# ir_remote_v3.net
KiCad netlist of a schematic drawn in EAGLE
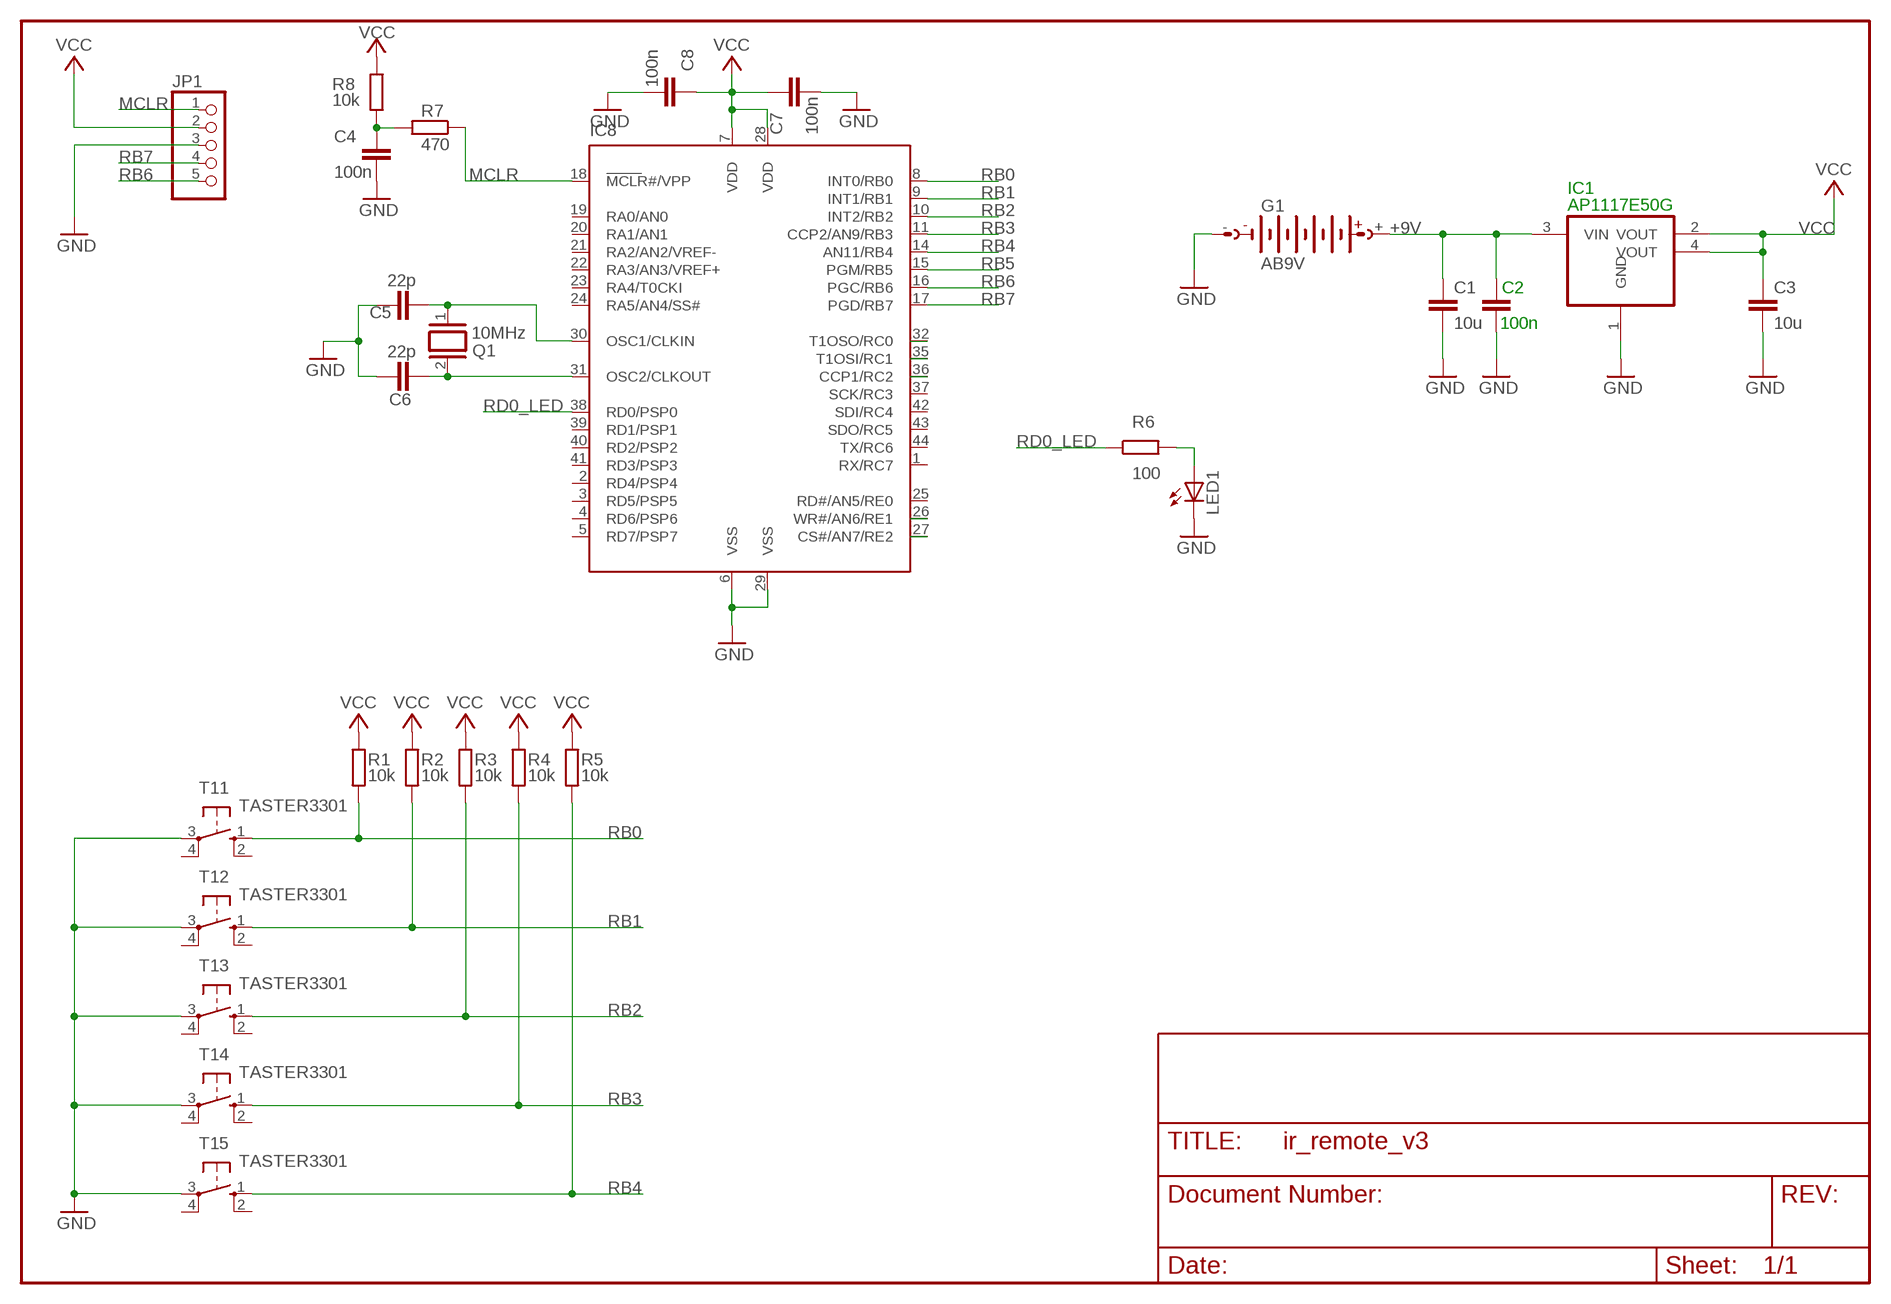
[diagram p0: schematic, sheet 1]

(export (version "E")
  (design (tool "Eeschema 10.0.6"))
  (components
    (comp (ref "C1")
      (value "10u")
      (footprint "eagle-import:C0805")
      (libsource (lib "eagle-import") (part "C-EUC0805"))
    )
    (comp (ref "C2")
      (value "100n")
      (footprint "eagle-import:C0805")
      (libsource (lib "eagle-import") (part "rcl_416_C-EUC0805"))
    )
    (comp (ref "C3")
      (value "10u")
      (footprint "eagle-import:C0805")
      (libsource (lib "eagle-import") (part "C-EUC0805"))
    )
    (comp (ref "C4")
      (value "100n")
      (footprint "eagle-import:C0805")
      (libsource (lib "eagle-import") (part "C-EUC0805"))
    )
    (comp (ref "C5")
      (value "22p")
      (footprint "eagle-import:C0603_WE")
      (libsource (lib "eagle-import") (part "C-EUC0603_WE"))
    )
    (comp (ref "C6")
      (value "22p")
      (footprint "eagle-import:C0603_WE")
      (libsource (lib "eagle-import") (part "C-EUC0603_WE"))
    )
    (comp (ref "C7")
      (value "100n")
      (footprint "eagle-import:C0805")
      (libsource (lib "eagle-import") (part "C-EUC0805"))
    )
    (comp (ref "C8")
      (value "100n")
      (footprint "eagle-import:C0805")
      (libsource (lib "eagle-import") (part "C-EUC0805"))
    )
    (comp (ref "G1")
      (value "AB9V")
      (footprint "eagle-import:AB9V")
      (libsource (lib "eagle-import") (part "AB9V"))
    )
    (comp (ref "IC1")
      (value "AP1117E50G")
      (footprint "eagle-import:SOT223")
      (libsource (lib "eagle-import") (part "REG1117-2OUT"))
    )
    (comp (ref "IC8")
      (value "PIC18F4520")
      (footprint "eagle-import:TQFP44")
      (libsource (lib "eagle-import") (part "PIC18F4520"))
    )
    (comp (ref "JP1")
      (value "PINHD-1X5")
      (footprint "eagle-import:1X05")
      (libsource (lib "eagle-import") (part "PINHD-1X5"))
    )
    (comp (ref "LED1")
      (value "LED5MM")
      (footprint "eagle-import:LED5MM")
      (libsource (lib "eagle-import") (part "LED5MM"))
    )
    (comp (ref "Q1")
      (value "10MHz")
      (footprint "eagle-import:QUARZ_HC5032_2")
      (libsource (lib "eagle-import") (part "XTAL_HC5032"))
    )
    (comp (ref "R1")
      (value "10k")
      (footprint "eagle-import:M0805")
      (libsource (lib "eagle-import") (part "R-EU_M0805"))
    )
    (comp (ref "R2")
      (value "10k")
      (footprint "eagle-import:M0805")
      (libsource (lib "eagle-import") (part "R-EU_M0805"))
    )
    (comp (ref "R3")
      (value "10k")
      (footprint "eagle-import:M0805")
      (libsource (lib "eagle-import") (part "R-EU_M0805"))
    )
    (comp (ref "R4")
      (value "10k")
      (footprint "eagle-import:M0805")
      (libsource (lib "eagle-import") (part "R-EU_M0805"))
    )
    (comp (ref "R5")
      (value "10k")
      (footprint "eagle-import:M0805")
      (libsource (lib "eagle-import") (part "R-EU_M0805"))
    )
    (comp (ref "R6")
      (value "100")
      (footprint "eagle-import:M0805")
      (libsource (lib "eagle-import") (part "R-EU_M0805"))
    )
    (comp (ref "R7")
      (value "470")
      (footprint "eagle-import:M0805")
      (libsource (lib "eagle-import") (part "R-EU_M0805"))
    )
    (comp (ref "R8")
      (value "10k")
      (footprint "eagle-import:M0805")
      (libsource (lib "eagle-import") (part "R-EU_M0805"))
    )
    (comp (ref "T11")
      (value "TASTER3301")
      (footprint "eagle-import:TASTER3301")
      (libsource (lib "eagle-import") (part "TASTER3301"))
    )
    (comp (ref "T12")
      (value "TASTER3301")
      (footprint "eagle-import:TASTER3301")
      (libsource (lib "eagle-import") (part "TASTER3301"))
    )
    (comp (ref "T13")
      (value "TASTER3301")
      (footprint "eagle-import:TASTER3301")
      (libsource (lib "eagle-import") (part "TASTER3301"))
    )
    (comp (ref "T14")
      (value "TASTER3301")
      (footprint "eagle-import:TASTER3301")
      (libsource (lib "eagle-import") (part "TASTER3301"))
    )
    (comp (ref "T15")
      (value "TASTER3301")
      (footprint "eagle-import:TASTER3301")
      (libsource (lib "eagle-import") (part "TASTER3301"))
    )
  )
  (nets
    (net (code "1") (name "/+9V") (class "Default")
      (node (ref "C1") (pin "1") (pinfunction "1_1") (pintype "passive"))
      (node (ref "C2") (pin "1") (pinfunction "1_1") (pintype "passive"))
      (node (ref "G1") (pin "+") (pinfunction "+_+") (pintype "passive"))
      (node (ref "IC1") (pin "3") (pinfunction "VIN_3") (pintype "input"))
    )
    (net (code "2") (name "/MCLR") (class "Default")
      (node (ref "IC8") (pin "18") (pinfunction "MCLR#/VPP_18") (pintype "input"))
      (node (ref "JP1") (pin "1") (pinfunction "1_1") (pintype "passive"))
      (node (ref "R7") (pin "1") (pinfunction "1_1") (pintype "passive"))
    )
    (net (code "3") (name "/RB0") (class "Default")
      (node (ref "IC8") (pin "8") (pinfunction "INT0/RB0_8") (pintype "bidirectional"))
      (node (ref "R1") (pin "2") (pinfunction "2_2") (pintype "passive"))
      (node (ref "T11") (pin "1") (pinfunction "S_1") (pintype "passive"))
    )
    (net (code "4") (name "/RB1") (class "Default")
      (node (ref "IC8") (pin "35") (pinfunction "T1OSI/RC1_35") (pintype "bidirectional"))
      (node (ref "IC8") (pin "9") (pinfunction "INT1/RB1_9") (pintype "bidirectional"))
      (node (ref "R2") (pin "2") (pinfunction "2_2") (pintype "passive"))
      (node (ref "T12") (pin "1") (pinfunction "S_1") (pintype "passive"))
    )
    (net (code "5") (name "/RB2") (class "Default")
      (node (ref "IC8") (pin "10") (pinfunction "INT2/RB2_10") (pintype "bidirectional"))
      (node (ref "IC8") (pin "32") (pinfunction "T1OSO/RC0_32") (pintype "bidirectional"))
      (node (ref "R3") (pin "2") (pinfunction "2_2") (pintype "passive"))
      (node (ref "T13") (pin "1") (pinfunction "S_1") (pintype "passive"))
    )
    (net (code "6") (name "/RB3") (class "Default")
      (node (ref "IC8") (pin "11") (pinfunction "CCP2/AN9/RB3_11") (pintype "bidirectional"))
      (node (ref "R4") (pin "2") (pinfunction "2_2") (pintype "passive"))
      (node (ref "T14") (pin "1") (pinfunction "S_1") (pintype "passive"))
    )
    (net (code "7") (name "/RB4") (class "Default")
      (node (ref "IC8") (pin "14") (pinfunction "AN11/RB4_14") (pintype "bidirectional"))
      (node (ref "R5") (pin "2") (pinfunction "2_2") (pintype "passive"))
      (node (ref "T15") (pin "1") (pinfunction "S_1") (pintype "passive"))
    )
    (net (code "8") (name "/RB5") (class "Default")
      (node (ref "IC8") (pin "15") (pinfunction "PGM/RB5_15") (pintype "bidirectional"))
    )
    (net (code "9") (name "/RB6") (class "Default")
      (node (ref "IC8") (pin "16") (pinfunction "PGC/RB6_16") (pintype "bidirectional"))
      (node (ref "JP1") (pin "5") (pinfunction "5_5") (pintype "passive"))
    )
    (net (code "10") (name "/RB7") (class "Default")
      (node (ref "IC8") (pin "17") (pinfunction "PGD/RB7_17") (pintype "bidirectional"))
      (node (ref "JP1") (pin "4") (pinfunction "4_4") (pintype "passive"))
    )
    (net (code "11") (name "/RD0_LED") (class "Default")
      (node (ref "IC8") (pin "38") (pinfunction "RD0/PSP0_38") (pintype "bidirectional"))
      (node (ref "R6") (pin "1") (pinfunction "1_1") (pintype "passive"))
    )
    (net (code "12") (name "GND") (class "Default")
      (node (ref "C1") (pin "2") (pinfunction "2_2") (pintype "passive"))
      (node (ref "C2") (pin "2") (pinfunction "2_2") (pintype "passive"))
      (node (ref "C3") (pin "2") (pinfunction "2_2") (pintype "passive"))
      (node (ref "C4") (pin "2") (pinfunction "2_2") (pintype "passive"))
      (node (ref "C5") (pin "1") (pinfunction "1_1") (pintype "passive"))
      (node (ref "C6") (pin "1") (pinfunction "1_1") (pintype "passive"))
      (node (ref "C7") (pin "2") (pinfunction "2_2") (pintype "passive"))
      (node (ref "C8") (pin "2") (pinfunction "2_2") (pintype "passive"))
      (node (ref "G1") (pin "-") (pinfunction "-_-") (pintype "passive"))
      (node (ref "IC1") (pin "1") (pinfunction "GND_1") (pintype "power_in"))
      (node (ref "IC8") (pin "29") (pinfunction "VSS_29") (pintype "bidirectional"))
      (node (ref "IC8") (pin "6") (pinfunction "VSS_6") (pintype "bidirectional"))
      (node (ref "JP1") (pin "3") (pinfunction "3_3") (pintype "passive"))
      (node (ref "LED1") (pin "K") (pinfunction "C_K") (pintype "passive"))
      (node (ref "T11") (pin "3") (pinfunction "P_3") (pintype "passive"))
      (node (ref "T12") (pin "3") (pinfunction "P_3") (pintype "passive"))
      (node (ref "T13") (pin "3") (pinfunction "P_3") (pintype "passive"))
      (node (ref "T14") (pin "3") (pinfunction "P_3") (pintype "passive"))
      (node (ref "T15") (pin "3") (pinfunction "P_3") (pintype "passive"))
    )
    (net (code "13") (name "Net-(C4-Pad1)") (class "Default")
      (node (ref "C4") (pin "1") (pinfunction "1_1") (pintype "passive"))
      (node (ref "R7") (pin "2") (pinfunction "2_2") (pintype "passive"))
      (node (ref "R8") (pin "2") (pinfunction "2_2") (pintype "passive"))
    )
    (net (code "14") (name "Net-(IC8-OSC1{slash}CLKIN)") (class "Default")
      (node (ref "C5") (pin "2") (pinfunction "2_2") (pintype "passive"))
      (node (ref "IC8") (pin "30") (pinfunction "OSC1/CLKIN_30") (pintype "input"))
      (node (ref "Q1") (pin "1") (pinfunction "1_1") (pintype "passive"))
    )
    (net (code "15") (name "Net-(IC8-OSC2{slash}CLKOUT)") (class "Default")
      (node (ref "C6") (pin "2") (pinfunction "2_2") (pintype "passive"))
      (node (ref "IC8") (pin "31") (pinfunction "OSC2/CLKOUT_31") (pintype "output"))
      (node (ref "Q1") (pin "2") (pinfunction "2_2") (pintype "passive"))
    )
    (net (code "16") (name "Net-(LED1-PadA)") (class "Default")
      (node (ref "LED1") (pin "A") (pinfunction "A_A") (pintype "passive"))
      (node (ref "R6") (pin "2") (pinfunction "2_2") (pintype "passive"))
    )
    (net (code "17") (name "VCC") (class "Default")
      (node (ref "C3") (pin "1") (pinfunction "1_1") (pintype "passive"))
      (node (ref "C7") (pin "1") (pinfunction "1_1") (pintype "passive"))
      (node (ref "C8") (pin "1") (pinfunction "1_1") (pintype "passive"))
      (node (ref "IC1") (pin "2") (pinfunction "VOUT_2") (pintype "output"))
      (node (ref "IC1") (pin "4") (pinfunction "VOUT_4") (pintype "bidirectional"))
      (node (ref "IC8") (pin "28") (pinfunction "VDD_28") (pintype "bidirectional"))
      (node (ref "IC8") (pin "7") (pinfunction "VDD_7") (pintype "bidirectional"))
      (node (ref "JP1") (pin "2") (pinfunction "2_2") (pintype "passive"))
      (node (ref "R1") (pin "1") (pinfunction "1_1") (pintype "passive"))
      (node (ref "R2") (pin "1") (pinfunction "1_1") (pintype "passive"))
      (node (ref "R3") (pin "1") (pinfunction "1_1") (pintype "passive"))
      (node (ref "R4") (pin "1") (pinfunction "1_1") (pintype "passive"))
      (node (ref "R5") (pin "1") (pinfunction "1_1") (pintype "passive"))
      (node (ref "R8") (pin "1") (pinfunction "1_1") (pintype "passive"))
    )
    (net (code "18") (name "unconnected-(IC8-CCP1{slash}RC2-Pad36)") (class "Default")
      (node (ref "IC8") (pin "36") (pinfunction "CCP1/RC2_36") (pintype "bidirectional"))
    )
    (net (code "19") (name "unconnected-(IC8-CS#{slash}AN7{slash}RE2-Pad27)") (class "Default")
      (node (ref "IC8") (pin "27") (pinfunction "CS#/AN7/RE2_27") (pintype "bidirectional"))
    )
    (net (code "20") (name "unconnected-(IC8-RA0{slash}AN0-Pad19)") (class "Default")
      (node (ref "IC8") (pin "19") (pinfunction "RA0/AN0_19") (pintype "bidirectional"))
    )
    (net (code "21") (name "unconnected-(IC8-RA1{slash}AN1-Pad20)") (class "Default")
      (node (ref "IC8") (pin "20") (pinfunction "RA1/AN1_20") (pintype "bidirectional"))
    )
    (net (code "22") (name "unconnected-(IC8-RA2{slash}AN2{slash}VREF--Pad21)") (class "Default")
      (node (ref "IC8") (pin "21") (pinfunction "RA2/AN2/VREF-_21") (pintype "bidirectional"))
    )
    (net (code "23") (name "unconnected-(IC8-RA3{slash}AN3{slash}VREF+-Pad22)") (class "Default")
      (node (ref "IC8") (pin "22") (pinfunction "RA3/AN3/VREF+_22") (pintype "bidirectional"))
    )
    (net (code "24") (name "unconnected-(IC8-RA4{slash}T0CKI-Pad23)") (class "Default")
      (node (ref "IC8") (pin "23") (pinfunction "RA4/T0CKI_23") (pintype "bidirectional"))
    )
    (net (code "25") (name "unconnected-(IC8-RA5{slash}AN4{slash}SS#-Pad24)") (class "Default")
      (node (ref "IC8") (pin "24") (pinfunction "RA5/AN4/SS#_24") (pintype "bidirectional"))
    )
    (net (code "26") (name "unconnected-(IC8-RD#{slash}AN5{slash}RE0-Pad25)") (class "Default")
      (node (ref "IC8") (pin "25") (pinfunction "RD#/AN5/RE0_25") (pintype "bidirectional"))
    )
    (net (code "27") (name "unconnected-(IC8-RD1{slash}PSP1-Pad39)") (class "Default")
      (node (ref "IC8") (pin "39") (pinfunction "RD1/PSP1_39") (pintype "bidirectional"))
    )
    (net (code "28") (name "unconnected-(IC8-RD2{slash}PSP2-Pad40)") (class "Default")
      (node (ref "IC8") (pin "40") (pinfunction "RD2/PSP2_40") (pintype "bidirectional"))
    )
    (net (code "29") (name "unconnected-(IC8-RD3{slash}PSP3-Pad41)") (class "Default")
      (node (ref "IC8") (pin "41") (pinfunction "RD3/PSP3_41") (pintype "bidirectional"))
    )
    (net (code "30") (name "unconnected-(IC8-RD4{slash}PSP4-Pad2)") (class "Default")
      (node (ref "IC8") (pin "2") (pinfunction "RD4/PSP4_2") (pintype "bidirectional"))
    )
    (net (code "31") (name "unconnected-(IC8-RD5{slash}PSP5-Pad3)") (class "Default")
      (node (ref "IC8") (pin "3") (pinfunction "RD5/PSP5_3") (pintype "bidirectional"))
    )
    (net (code "32") (name "unconnected-(IC8-RD6{slash}PSP6-Pad4)") (class "Default")
      (node (ref "IC8") (pin "4") (pinfunction "RD6/PSP6_4") (pintype "bidirectional"))
    )
    (net (code "33") (name "unconnected-(IC8-RD7{slash}PSP7-Pad5)") (class "Default")
      (node (ref "IC8") (pin "5") (pinfunction "RD7/PSP7_5") (pintype "bidirectional"))
    )
    (net (code "34") (name "unconnected-(IC8-RX{slash}RC7-Pad1)") (class "Default")
      (node (ref "IC8") (pin "1") (pinfunction "RX/RC7_1") (pintype "bidirectional"))
    )
    (net (code "35") (name "unconnected-(IC8-SCK{slash}RC3-Pad37)") (class "Default")
      (node (ref "IC8") (pin "37") (pinfunction "SCK/RC3_37") (pintype "bidirectional"))
    )
    (net (code "36") (name "unconnected-(IC8-SDI{slash}RC4-Pad42)") (class "Default")
      (node (ref "IC8") (pin "42") (pinfunction "SDI/RC4_42") (pintype "bidirectional"))
    )
    (net (code "37") (name "unconnected-(IC8-SDO{slash}RC5-Pad43)") (class "Default")
      (node (ref "IC8") (pin "43") (pinfunction "SDO/RC5_43") (pintype "bidirectional"))
    )
    (net (code "38") (name "unconnected-(IC8-TX{slash}RC6-Pad44)") (class "Default")
      (node (ref "IC8") (pin "44") (pinfunction "TX/RC6_44") (pintype "bidirectional"))
    )
    (net (code "39") (name "unconnected-(IC8-WR#{slash}AN6{slash}RE1-Pad26)") (class "Default")
      (node (ref "IC8") (pin "26") (pinfunction "WR#/AN6/RE1_26") (pintype "bidirectional"))
    )
    (net (code "40") (name "unconnected-(T11-P1-Pad4)") (class "Default")
      (node (ref "T11") (pin "4") (pinfunction "P1_4") (pintype "passive"))
    )
    (net (code "41") (name "unconnected-(T11-S1-Pad2)") (class "Default")
      (node (ref "T11") (pin "2") (pinfunction "S1_2") (pintype "passive"))
    )
    (net (code "42") (name "unconnected-(T12-P1-Pad4)") (class "Default")
      (node (ref "T12") (pin "4") (pinfunction "P1_4") (pintype "passive"))
    )
    (net (code "43") (name "unconnected-(T12-S1-Pad2)") (class "Default")
      (node (ref "T12") (pin "2") (pinfunction "S1_2") (pintype "passive"))
    )
    (net (code "44") (name "unconnected-(T13-P1-Pad4)") (class "Default")
      (node (ref "T13") (pin "4") (pinfunction "P1_4") (pintype "passive"))
    )
    (net (code "45") (name "unconnected-(T13-S1-Pad2)") (class "Default")
      (node (ref "T13") (pin "2") (pinfunction "S1_2") (pintype "passive"))
    )
    (net (code "46") (name "unconnected-(T14-P1-Pad4)") (class "Default")
      (node (ref "T14") (pin "4") (pinfunction "P1_4") (pintype "passive"))
    )
    (net (code "47") (name "unconnected-(T14-S1-Pad2)") (class "Default")
      (node (ref "T14") (pin "2") (pinfunction "S1_2") (pintype "passive"))
    )
    (net (code "48") (name "unconnected-(T15-P1-Pad4)") (class "Default")
      (node (ref "T15") (pin "4") (pinfunction "P1_4") (pintype "passive"))
    )
    (net (code "49") (name "unconnected-(T15-S1-Pad2)") (class "Default")
      (node (ref "T15") (pin "2") (pinfunction "S1_2") (pintype "passive"))
    )
  )
)
